# Heater_020305.net
KiCad netlist of a schematic drawn in Altium Designer
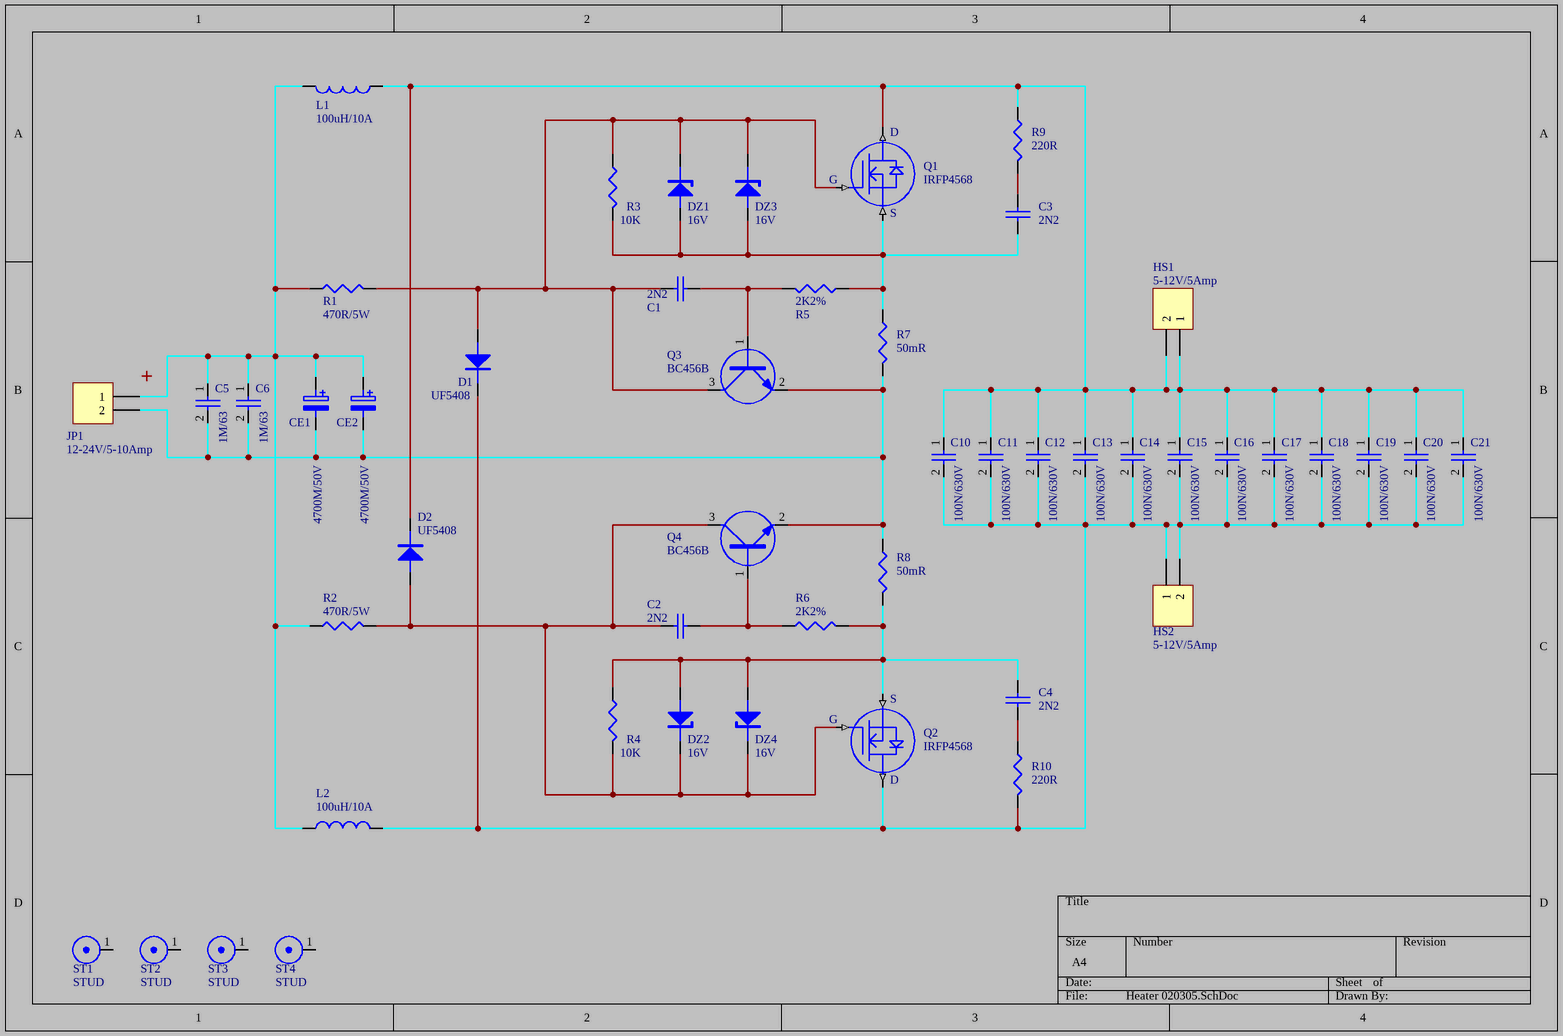
[diagram p0: Heater 020305.SchDoc]

(export (version "E")
  (design (tool "Eeschema 10.0.6"))
  (components
    (comp (ref "C1") (value "2N2") (footprint "C2P") (libsource (lib "MyAltiumLib97_V0.4") (part "C")))
    (comp (ref "C2") (value "2N2") (footprint "C2P") (libsource (lib "MyAltiumLib97_V0.4") (part "C")))
    (comp (ref "C3") (value "2N2") (footprint "C2P") (libsource (lib "MyAltiumLib97_V0.4") (part "C")))
    (comp (ref "C4") (value "2N2") (footprint "C2P") (libsource (lib "MyAltiumLib97_V0.4") (part "C")))
    (comp (ref "C5") (value "1M/63") (footprint "C3P") (libsource (lib "1402 Schlib 2020") (part "C")))
    (comp (ref "C6") (value "1M/63") (footprint "C3P") (libsource (lib "1402 Schlib 2020") (part "C")))
    (comp (ref "C10")
      (value "100N/630V")
      (footprint "CV25-8-22")
      (libsource (lib "1402 Schlib 2020") (part "C"))
    )
    (comp (ref "C11")
      (value "100N/630V")
      (footprint "CV25-8-22")
      (libsource (lib "1402 Schlib 2020") (part "C"))
    )
    (comp (ref "C12")
      (value "100N/630V")
      (footprint "CV25-8-22")
      (libsource (lib "1402 Schlib 2020") (part "C"))
    )
    (comp (ref "C13")
      (value "100N/630V")
      (footprint "CV25-8-22")
      (libsource (lib "1402 Schlib 2020") (part "C"))
    )
    (comp (ref "C14")
      (value "100N/630V")
      (footprint "CV25-8-22")
      (libsource (lib "1402 Schlib 2020") (part "C"))
    )
    (comp (ref "C15")
      (value "100N/630V")
      (footprint "CV25-8-22")
      (libsource (lib "1402 Schlib 2020") (part "C"))
    )
    (comp (ref "C16")
      (value "100N/630V")
      (footprint "CV25-8-22")
      (libsource (lib "1402 Schlib 2020") (part "C"))
    )
    (comp (ref "C17")
      (value "100N/630V")
      (footprint "CV25-8-22")
      (libsource (lib "1402 Schlib 2020") (part "C"))
    )
    (comp (ref "C18")
      (value "100N/630V")
      (footprint "CV25-8-22")
      (libsource (lib "1402 Schlib 2020") (part "C"))
    )
    (comp (ref "C19")
      (value "100N/630V")
      (footprint "CV25-8-22")
      (libsource (lib "1402 Schlib 2020") (part "C"))
    )
    (comp (ref "C20")
      (value "100N/630V")
      (footprint "CV25-8-22")
      (libsource (lib "1402 Schlib 2020") (part "C"))
    )
    (comp (ref "C21")
      (value "100N/630V")
      (footprint "CV25-8-22")
      (libsource (lib "1402 Schlib 2020") (part "C"))
    )
    (comp (ref "CE1") (value "4700M/50V") (footprint "CAP3P") (libsource (lib "1402 Schlib 2020") (part "E")))
    (comp (ref "CE2") (value "4700M/50V") (footprint "CAP3P") (libsource (lib "1402 Schlib 2020") (part "E")))
    (comp (ref "D1") (value "UF5408") (footprint "D54") (libsource (lib "MyAltiumLib9702") (part "D")))
    (comp (ref "D2") (value "UF5408") (footprint "D54") (libsource (lib "MyAltiumLib9702") (part "D")))
    (comp (ref "DZ1") (value "16V") (footprint "D4P") (libsource (lib "MyAltiumLib9702") (part "DZ")))
    (comp (ref "DZ2") (value "16V") (footprint "D4P") (libsource (lib "MyAltiumLib9702") (part "DZ")))
    (comp (ref "DZ3") (value "16V") (footprint "D4P") (libsource (lib "MyAltiumLib9702") (part "DZ")))
    (comp (ref "DZ4") (value "16V") (footprint "D4P") (libsource (lib "MyAltiumLib9702") (part "DZ")))
    (comp (ref "HS1")
      (value "5-12V/5Amp")
      (footprint "HS1")
      (description "Header, 2-Pin")
      (fields (field (name "PUBLISHER") "Altium Limited"))
      (libsource (lib "") (part "Header 2_1"))
    )
    (comp (ref "HS2")
      (value "5-12V/5Amp")
      (footprint "HS1")
      (description "Header, 2-Pin")
      (fields (field (name "PUBLISHER") "Altium Limited"))
      (libsource (lib "Miscellaneous Connectors") (part "Header 2"))
    )
    (comp (ref "JP1")
      (value "12-24V/5-10Amp")
      (footprint "DG55X2")
      (description "Header, 2-Pin")
      (fields (field (name "PUBLISHER") "Altium Limited"))
      (libsource (lib "") (part "Header 2_2"))
    )
    (comp (ref "L1")
      (value "100uH/10A")
      (footprint "INDU2511")
      (libsource (lib "MyAltiumLib9702") (part "INDUCTOR"))
    )
    (comp (ref "L2") (value "100uH/10A") (footprint "INDU2511") (libsource (lib "") (part "INDUCTOR_1")))
    (comp (ref "Q1")
      (value "IRFP4568")
      (footprint "TO247-MOSPIN")
      (libsource (lib "1402 Schlib 2020") (part "MOSFET N"))
    )
    (comp (ref "Q2")
      (value "IRFP4568")
      (footprint "TO247-MOSPIN")
      (libsource (lib "1402 Schlib 2020") (part "MOSFET N"))
    )
    (comp (ref "Q3") (value "BC456B") (footprint "CBE-BC546") (libsource (lib "MyAltiumLib95") (part "N")))
    (comp (ref "Q4") (value "BC456B") (footprint "CBE-BC546") (libsource (lib "MyAltiumLib95") (part "N")))
    (comp (ref "R1") (value "470R/5W") (footprint "W5") (libsource (lib "*") (part "R")))
    (comp (ref "R2") (value "470R/5W") (footprint "W5") (libsource (lib "*") (part "R")))
    (comp (ref "R3") (value "10K") (footprint "R4P") (libsource (lib "*") (part "R")))
    (comp (ref "R4") (value "10K") (footprint "R4P") (libsource (lib "*") (part "R")))
    (comp (ref "R5") (value "2K2%") (footprint "R4P") (libsource (lib "*") (part "R")))
    (comp (ref "R6") (value "2K2%") (footprint "R4P") (libsource (lib "*") (part "R")))
    (comp (ref "R7") (value "50mR") (footprint "WIRE1m5") (libsource (lib "*") (part "R")))
    (comp (ref "R8") (value "50mR") (footprint "WIRE1m5") (libsource (lib "*") (part "R")))
    (comp (ref "R9") (value "220R") (footprint "W5") (libsource (lib "*") (part "R")))
    (comp (ref "R10") (value "220R") (footprint "W5") (libsource (lib "*") (part "R")))
    (comp (ref "ST1") (value "STUD") (footprint "CORNER") (libsource (lib "1402 Schlib 2020") (part "STUD")))
    (comp (ref "ST2") (value "STUD") (footprint "CORNER") (libsource (lib "1402 Schlib 2020") (part "STUD")))
    (comp (ref "ST3") (value "STUD") (footprint "CORNER") (libsource (lib "1402 Schlib 2020") (part "STUD")))
    (comp (ref "ST4") (value "STUD") (footprint "CORNER") (libsource (lib "1402 Schlib 2020") (part "STUD")))
  )
  (nets
    (net (code "1") (name "Net-(C3-Pad1)") (class "Default")
      (node (ref "C3") (pin "1") (pintype "passive"))
      (node (ref "R9") (pin "1") (pintype "passive"))
    )
    (net (code "2") (name "Net-(C4-Pad1)") (class "Default")
      (node (ref "C4") (pin "1") (pintype "passive"))
      (node (ref "R10") (pin "2") (pintype "passive"))
    )
    (net (code "3") (name "Net-(C5-Pad1)") (class "Default")
      (node (ref "C5") (pin "1") (pintype "passive"))
      (node (ref "C6") (pin "1") (pintype "passive"))
      (node (ref "CE1") (pin "1") (pintype "passive"))
      (node (ref "CE2") (pin "1") (pintype "passive"))
      (node (ref "JP1") (pin "1") (pinfunction "1_1") (pintype "passive"))
      (node (ref "L1") (pin "1") (pinfunction "1_1") (pintype "passive"))
      (node (ref "L2") (pin "1") (pinfunction "1_1") (pintype "passive"))
      (node (ref "R1") (pin "1") (pintype "passive"))
      (node (ref "R2") (pin "1") (pintype "passive"))
    )
    (net (code "4") (name "Net-(D1-A)") (class "Default")
      (node (ref "C1") (pin "2") (pintype "passive"))
      (node (ref "D1") (pin "1") (pinfunction "A_1") (pintype "passive"))
      (node (ref "DZ1") (pin "2") (pinfunction "K_2") (pintype "passive"))
      (node (ref "DZ3") (pin "2") (pinfunction "K_2") (pintype "passive"))
      (node (ref "Q1") (pin "1") (pinfunction "G_1") (pintype "input"))
      (node (ref "Q3") (pin "3") (pinfunction "C_3") (pintype "passive"))
      (node (ref "R1") (pin "2") (pintype "passive"))
      (node (ref "R3") (pin "1") (pintype "passive"))
    )
    (net (code "5") (name "Net-(D1-K)") (class "Default")
      (node (ref "C10") (pin "2") (pintype "passive"))
      (node (ref "C11") (pin "2") (pintype "passive"))
      (node (ref "C12") (pin "2") (pintype "passive"))
      (node (ref "C13") (pin "2") (pintype "passive"))
      (node (ref "C14") (pin "2") (pintype "passive"))
      (node (ref "C15") (pin "2") (pintype "passive"))
      (node (ref "C16") (pin "2") (pintype "passive"))
      (node (ref "C17") (pin "2") (pintype "passive"))
      (node (ref "C18") (pin "2") (pintype "passive"))
      (node (ref "C19") (pin "2") (pintype "passive"))
      (node (ref "C20") (pin "2") (pintype "passive"))
      (node (ref "C21") (pin "2") (pintype "passive"))
      (node (ref "D1") (pin "2") (pinfunction "K_2") (pintype "passive"))
      (node (ref "HS2") (pin "1") (pinfunction "1_1") (pintype "passive"))
      (node (ref "HS2") (pin "2") (pinfunction "2_2") (pintype "passive"))
      (node (ref "L2") (pin "2") (pinfunction "2_2") (pintype "passive"))
      (node (ref "Q2") (pin "2") (pinfunction "D_2") (pintype "output"))
      (node (ref "R10") (pin "1") (pintype "passive"))
    )
    (net (code "6") (name "Net-(D2-A)") (class "Default")
      (node (ref "C2") (pin "2") (pintype "passive"))
      (node (ref "D2") (pin "1") (pinfunction "A_1") (pintype "passive"))
      (node (ref "DZ2") (pin "2") (pinfunction "K_2") (pintype "passive"))
      (node (ref "DZ4") (pin "2") (pinfunction "K_2") (pintype "passive"))
      (node (ref "Q2") (pin "1") (pinfunction "G_1") (pintype "input"))
      (node (ref "Q4") (pin "3") (pinfunction "C_3") (pintype "passive"))
      (node (ref "R2") (pin "2") (pintype "passive"))
      (node (ref "R4") (pin "2") (pintype "passive"))
    )
    (net (code "7") (name "Net-(D2-K)") (class "Default")
      (node (ref "C10") (pin "1") (pintype "passive"))
      (node (ref "C11") (pin "1") (pintype "passive"))
      (node (ref "C12") (pin "1") (pintype "passive"))
      (node (ref "C13") (pin "1") (pintype "passive"))
      (node (ref "C14") (pin "1") (pintype "passive"))
      (node (ref "C15") (pin "1") (pintype "passive"))
      (node (ref "C16") (pin "1") (pintype "passive"))
      (node (ref "C17") (pin "1") (pintype "passive"))
      (node (ref "C18") (pin "1") (pintype "passive"))
      (node (ref "C19") (pin "1") (pintype "passive"))
      (node (ref "C20") (pin "1") (pintype "passive"))
      (node (ref "C21") (pin "1") (pintype "passive"))
      (node (ref "D2") (pin "2") (pinfunction "K_2") (pintype "passive"))
      (node (ref "HS1") (pin "1") (pinfunction "1_1") (pintype "passive"))
      (node (ref "HS1") (pin "2") (pinfunction "2_2") (pintype "passive"))
      (node (ref "L1") (pin "2") (pinfunction "2_2") (pintype "passive"))
      (node (ref "Q1") (pin "2") (pinfunction "D_2") (pintype "output"))
      (node (ref "R9") (pin "2") (pintype "passive"))
    )
    (net (code "8") (name "Net-(DZ1-A)") (class "Default")
      (node (ref "C3") (pin "2") (pintype "passive"))
      (node (ref "DZ1") (pin "1") (pinfunction "A_1") (pintype "passive"))
      (node (ref "DZ3") (pin "1") (pinfunction "A_1") (pintype "passive"))
      (node (ref "Q1") (pin "3") (pinfunction "S_3") (pintype "input"))
      (node (ref "R3") (pin "2") (pintype "passive"))
      (node (ref "R5") (pin "1") (pintype "passive"))
      (node (ref "R7") (pin "1") (pintype "passive"))
    )
    (net (code "9") (name "Net-(DZ2-A)") (class "Default")
      (node (ref "C4") (pin "2") (pintype "passive"))
      (node (ref "DZ2") (pin "1") (pinfunction "A_1") (pintype "passive"))
      (node (ref "DZ4") (pin "1") (pinfunction "A_1") (pintype "passive"))
      (node (ref "Q2") (pin "3") (pinfunction "S_3") (pintype "input"))
      (node (ref "R4") (pin "1") (pintype "passive"))
      (node (ref "R6") (pin "1") (pintype "passive"))
      (node (ref "R8") (pin "1") (pintype "passive"))
    )
    (net (code "10") (name "Net-(Q3-B)") (class "Default")
      (node (ref "C1") (pin "1") (pintype "passive"))
      (node (ref "Q3") (pin "1") (pinfunction "B_1") (pintype "passive"))
      (node (ref "R5") (pin "2") (pintype "passive"))
    )
    (net (code "11") (name "Net-(Q3-E)") (class "Default")
      (node (ref "C5") (pin "2") (pintype "passive"))
      (node (ref "C6") (pin "2") (pintype "passive"))
      (node (ref "CE1") (pin "2") (pintype "passive"))
      (node (ref "CE2") (pin "2") (pintype "passive"))
      (node (ref "JP1") (pin "2") (pinfunction "2_2") (pintype "passive"))
      (node (ref "Q3") (pin "2") (pinfunction "E_2") (pintype "passive"))
      (node (ref "Q4") (pin "2") (pinfunction "E_2") (pintype "passive"))
      (node (ref "R7") (pin "2") (pintype "passive"))
      (node (ref "R8") (pin "2") (pintype "passive"))
    )
    (net (code "12") (name "Net-(Q4-B)") (class "Default")
      (node (ref "C2") (pin "1") (pintype "passive"))
      (node (ref "Q4") (pin "1") (pinfunction "B_1") (pintype "passive"))
      (node (ref "R6") (pin "2") (pintype "passive"))
    )
    (net (code "13") (name "unconnected-(ST1-Pad1)") (class "Default")
      (node (ref "ST1") (pin "1") (pintype "passive"))
    )
    (net (code "14") (name "unconnected-(ST2-Pad1)") (class "Default")
      (node (ref "ST2") (pin "1") (pintype "passive"))
    )
    (net (code "15") (name "unconnected-(ST3-Pad1)") (class "Default")
      (node (ref "ST3") (pin "1") (pintype "passive"))
    )
    (net (code "16") (name "unconnected-(ST4-Pad1)") (class "Default")
      (node (ref "ST4") (pin "1") (pintype "passive"))
    )
  )
)
